# MTRduino_Rev1_0.net
KiCad netlist of a schematic drawn in EAGLE
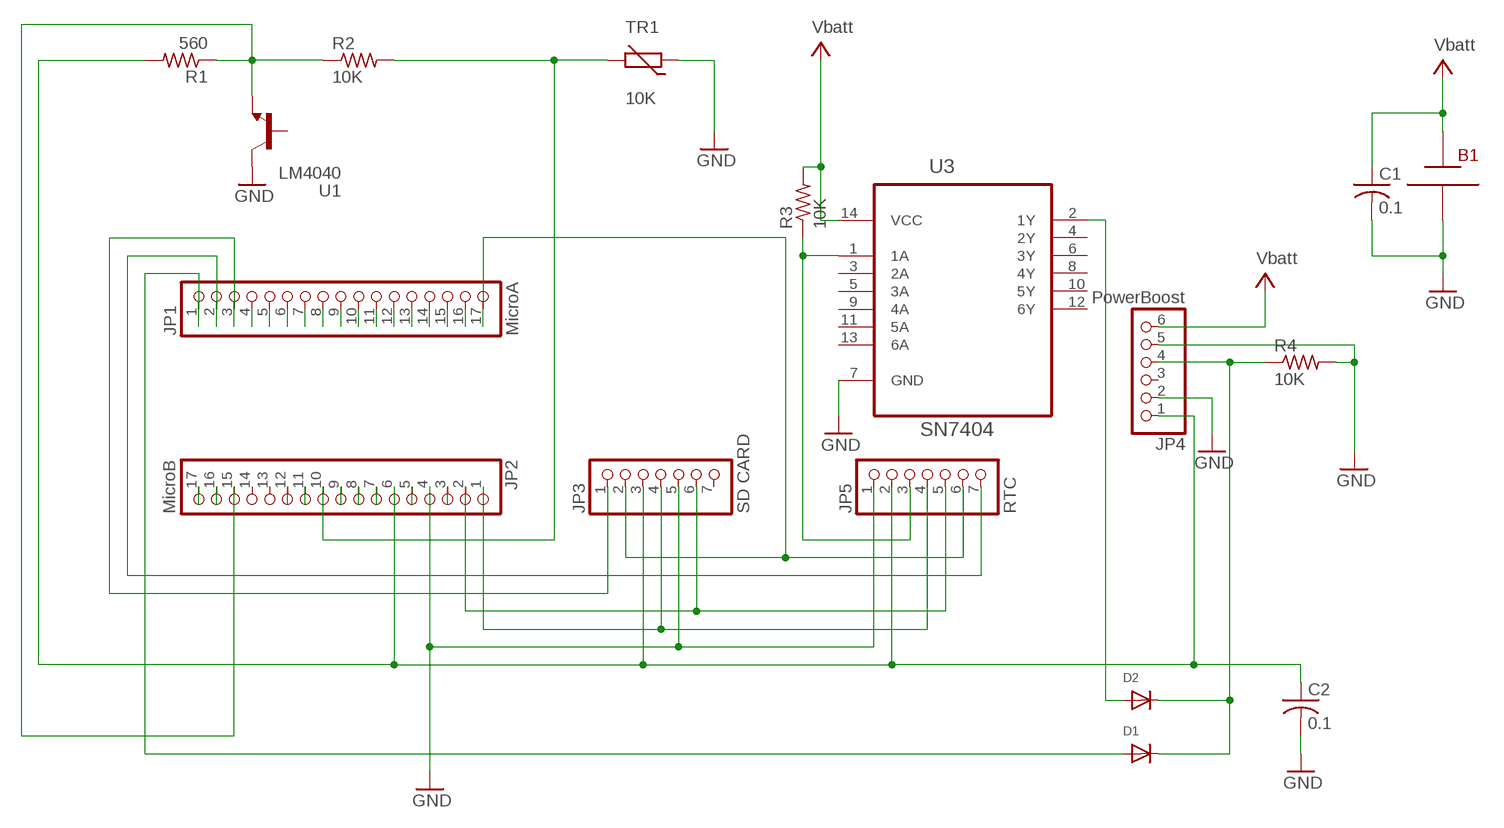
[diagram p0: schematic, sheet 1]

(export (version "E")
  (design (tool "Eeschema 10.0.6"))
  (components
    (comp (ref "B1")
      (value "AA Batt")
      (footprint "eagle-import:BATT_AA2")
      (libsource (lib "eagle-import") (part "BATT_AA2"))
    )
    (comp (ref "C1")
      (value "0.1")
      (footprint "eagle-import:C025-030X050")
      (libsource (lib "eagle-import") (part "C-US025-030X050"))
    )
    (comp (ref "C2")
      (value "0.1")
      (footprint "eagle-import:C025-030X050")
      (libsource (lib "eagle-import") (part "C-US025-030X050"))
    )
    (comp (ref "D1")
      (value "DIODEDO-1N4148")
      (footprint "eagle-import:DO-1N4148")
      (libsource (lib "eagle-import") (part "DIODEDO-1N4148"))
    )
    (comp (ref "D2")
      (value "DIODEDO-1N4148")
      (footprint "eagle-import:DO-1N4148")
      (libsource (lib "eagle-import") (part "DIODEDO-1N4148"))
    )
    (comp (ref "JP1")
      (value "MicroA")
      (footprint "eagle-import:1X17")
      (libsource (lib "eagle-import") (part "PINHD-1X17"))
    )
    (comp (ref "JP2")
      (value "MicroB")
      (footprint "eagle-import:1X17")
      (libsource (lib "eagle-import") (part "PINHD-1X17"))
    )
    (comp (ref "JP3")
      (value "SD CARD")
      (footprint "eagle-import:1X07")
      (libsource (lib "eagle-import") (part "PINHD-1X7"))
    )
    (comp (ref "JP4")
      (value "PowerBoost")
      (footprint "eagle-import:1X06")
      (libsource (lib "eagle-import") (part "PINHD-1X6"))
    )
    (comp (ref "JP5")
      (value "RTC")
      (footprint "eagle-import:1X07")
      (libsource (lib "eagle-import") (part "PINHD-1X7"))
    )
    (comp (ref "R1")
      (value "560")
      (footprint "eagle-import:0207_12")
      (libsource (lib "eagle-import") (part "R-US_0207/12"))
    )
    (comp (ref "R2")
      (value "10K")
      (footprint "eagle-import:0207_12")
      (libsource (lib "eagle-import") (part "R-US_0207/12"))
    )
    (comp (ref "R3")
      (value "10K")
      (footprint "eagle-import:0207_12")
      (libsource (lib "eagle-import") (part "R-US_0207/12"))
    )
    (comp (ref "R4")
      (value "10K")
      (footprint "eagle-import:0207_12")
      (libsource (lib "eagle-import") (part "R-US_0207/12"))
    )
    (comp (ref "TR1")
      (value "10K")
      (footprint "eagle-import:R-5")
      (libsource (lib "eagle-import") (part "THERMISTOR-5"))
    )
    (comp (ref "U1")
      (value "LM4040")
      (footprint "eagle-import:TO92-BEC")
      (libsource (lib "eagle-import") (part "-NPN-TO92-BEC"))
    )
    (comp (ref "U3")
      (value "SN7404")
      (footprint "eagle-import:DIP254P762X508-14")
      (fields (field (name "MPN") "SN74AC04N"))
      (libsource (lib "eagle-import") (part "SN74AC04N"))
    )
  )
  (nets
    (net (code "1") (name "GND") (class "Default")
      (node (ref "B1") (pin "-") (pinfunction "-_-") (pintype "bidirectional"))
      (node (ref "C1") (pin "2") (pinfunction "2_2") (pintype "passive"))
      (node (ref "C2") (pin "2") (pinfunction "2_2") (pintype "passive"))
      (node (ref "JP2") (pin "4") (pinfunction "4_4") (pintype "passive"))
      (node (ref "JP3") (pin "5") (pinfunction "5_5") (pintype "passive"))
      (node (ref "JP4") (pin "2") (pinfunction "2_2") (pintype "passive"))
      (node (ref "JP4") (pin "5") (pinfunction "5_5") (pintype "passive"))
      (node (ref "JP5") (pin "1") (pinfunction "1_1") (pintype "passive"))
      (node (ref "R4") (pin "2") (pinfunction "2_2") (pintype "passive"))
      (node (ref "TR1") (pin "1") (pinfunction "1_1") (pintype "passive"))
      (node (ref "U1") (pin "C") (pinfunction "C_C") (pintype "passive"))
      (node (ref "U3") (pin "7") (pinfunction "GND_7") (pintype "passive"))
    )
    (net (code "2") (name "Net-(C2-Pad1)") (class "Default")
      (node (ref "C2") (pin "1") (pinfunction "1_1") (pintype "passive"))
      (node (ref "JP2") (pin "6") (pinfunction "6_6") (pintype "passive"))
      (node (ref "JP3") (pin "3") (pinfunction "3_3") (pintype "passive"))
      (node (ref "JP4") (pin "1") (pinfunction "1_1") (pintype "passive"))
      (node (ref "JP5") (pin "2") (pinfunction "2_2") (pintype "passive"))
      (node (ref "R1") (pin "2") (pinfunction "2_2") (pintype "passive"))
    )
    (net (code "3") (name "Net-(D1-PadA)") (class "Default")
      (node (ref "D1") (pin "A") (pinfunction "A_A") (pintype "passive"))
      (node (ref "JP1") (pin "1") (pinfunction "1_1") (pintype "passive"))
    )
    (net (code "4") (name "Net-(D1-PadC)") (class "Default")
      (node (ref "D1") (pin "C") (pinfunction "C_C") (pintype "passive"))
      (node (ref "D2") (pin "C") (pinfunction "C_C") (pintype "passive"))
      (node (ref "JP4") (pin "4") (pinfunction "4_4") (pintype "passive"))
      (node (ref "R4") (pin "1") (pinfunction "1_1") (pintype "passive"))
    )
    (net (code "5") (name "Net-(JP1-Pad2)") (class "Default")
      (node (ref "JP1") (pin "2") (pinfunction "2_2") (pintype "passive"))
      (node (ref "JP5") (pin "7") (pinfunction "7_7") (pintype "passive"))
    )
    (net (code "6") (name "Net-(JP1-Pad3)") (class "Default")
      (node (ref "JP1") (pin "3") (pinfunction "3_3") (pintype "passive"))
      (node (ref "JP3") (pin "1") (pinfunction "1_1") (pintype "passive"))
    )
    (net (code "7") (name "Net-(JP1-Pad17)") (class "Default")
      (node (ref "JP1") (pin "17") (pinfunction "17_17") (pintype "passive"))
      (node (ref "JP3") (pin "2") (pinfunction "2_2") (pintype "passive"))
      (node (ref "JP5") (pin "6") (pinfunction "6_6") (pintype "passive"))
    )
    (net (code "8") (name "Net-(JP2-Pad1)") (class "Default")
      (node (ref "JP2") (pin "1") (pinfunction "1_1") (pintype "passive"))
      (node (ref "JP3") (pin "4") (pinfunction "4_4") (pintype "passive"))
      (node (ref "JP5") (pin "4") (pinfunction "4_4") (pintype "passive"))
    )
    (net (code "9") (name "Net-(JP2-Pad2)") (class "Default")
      (node (ref "JP2") (pin "2") (pinfunction "2_2") (pintype "passive"))
      (node (ref "JP3") (pin "6") (pinfunction "6_6") (pintype "passive"))
      (node (ref "JP5") (pin "5") (pinfunction "5_5") (pintype "passive"))
    )
    (net (code "10") (name "Net-(JP2-Pad10)") (class "Default")
      (node (ref "JP2") (pin "10") (pinfunction "10_10") (pintype "passive"))
      (node (ref "R2") (pin "2") (pinfunction "2_2") (pintype "passive"))
      (node (ref "TR1") (pin "2") (pinfunction "2_2") (pintype "passive"))
    )
    (net (code "11") (name "Net-(JP2-Pad15)") (class "Default")
      (node (ref "JP2") (pin "15") (pinfunction "15_15") (pintype "passive"))
      (node (ref "R1") (pin "1") (pinfunction "1_1") (pintype "passive"))
      (node (ref "R2") (pin "1") (pinfunction "1_1") (pintype "passive"))
      (node (ref "U1") (pin "E") (pinfunction "E_E") (pintype "passive"))
    )
    (net (code "12") (name "Net-(U3-1A)") (class "Default")
      (node (ref "JP5") (pin "3") (pinfunction "3_3") (pintype "passive"))
      (node (ref "R3") (pin "1") (pinfunction "1_1") (pintype "passive"))
      (node (ref "U3") (pin "1") (pinfunction "1A_1") (pintype "input"))
    )
    (net (code "13") (name "Net-(U3-1Y)") (class "Default")
      (node (ref "D2") (pin "A") (pinfunction "A_A") (pintype "passive"))
      (node (ref "U3") (pin "2") (pinfunction "1Y_2") (pintype "output"))
    )
    (net (code "14") (name "Vbatt") (class "Default")
      (node (ref "B1") (pin "+") (pinfunction "+_+") (pintype "bidirectional"))
      (node (ref "C1") (pin "1") (pinfunction "1_1") (pintype "passive"))
      (node (ref "JP4") (pin "6") (pinfunction "6_6") (pintype "passive"))
      (node (ref "R3") (pin "2") (pinfunction "2_2") (pintype "passive"))
      (node (ref "U3") (pin "14") (pinfunction "VCC_14") (pintype "power_in"))
    )
    (net (code "15") (name "unconnected-(JP1-Pad4)") (class "Default")
      (node (ref "JP1") (pin "4") (pinfunction "4_4") (pintype "passive"))
    )
    (net (code "16") (name "unconnected-(JP1-Pad5)") (class "Default")
      (node (ref "JP1") (pin "5") (pinfunction "5_5") (pintype "passive"))
    )
    (net (code "17") (name "unconnected-(JP1-Pad6)") (class "Default")
      (node (ref "JP1") (pin "6") (pinfunction "6_6") (pintype "passive"))
    )
    (net (code "18") (name "unconnected-(JP1-Pad7)") (class "Default")
      (node (ref "JP1") (pin "7") (pinfunction "7_7") (pintype "passive"))
    )
    (net (code "19") (name "unconnected-(JP1-Pad8)") (class "Default")
      (node (ref "JP1") (pin "8") (pinfunction "8_8") (pintype "passive"))
    )
    (net (code "20") (name "unconnected-(JP1-Pad9)") (class "Default")
      (node (ref "JP1") (pin "9") (pinfunction "9_9") (pintype "passive"))
    )
    (net (code "21") (name "unconnected-(JP1-Pad10)") (class "Default")
      (node (ref "JP1") (pin "10") (pinfunction "10_10") (pintype "passive"))
    )
    (net (code "22") (name "unconnected-(JP1-Pad11)") (class "Default")
      (node (ref "JP1") (pin "11") (pinfunction "11_11") (pintype "passive"))
    )
    (net (code "23") (name "unconnected-(JP1-Pad12)") (class "Default")
      (node (ref "JP1") (pin "12") (pinfunction "12_12") (pintype "passive"))
    )
    (net (code "24") (name "unconnected-(JP1-Pad13)") (class "Default")
      (node (ref "JP1") (pin "13") (pinfunction "13_13") (pintype "passive"))
    )
    (net (code "25") (name "unconnected-(JP1-Pad14)") (class "Default")
      (node (ref "JP1") (pin "14") (pinfunction "14_14") (pintype "passive"))
    )
    (net (code "26") (name "unconnected-(JP1-Pad15)") (class "Default")
      (node (ref "JP1") (pin "15") (pinfunction "15_15") (pintype "passive"))
    )
    (net (code "27") (name "unconnected-(JP1-Pad16)") (class "Default")
      (node (ref "JP1") (pin "16") (pinfunction "16_16") (pintype "passive"))
    )
    (net (code "28") (name "unconnected-(JP2-Pad3)") (class "Default")
      (node (ref "JP2") (pin "3") (pinfunction "3_3") (pintype "passive"))
    )
    (net (code "29") (name "unconnected-(JP2-Pad5)") (class "Default")
      (node (ref "JP2") (pin "5") (pinfunction "5_5") (pintype "passive"))
    )
    (net (code "30") (name "unconnected-(JP2-Pad7)") (class "Default")
      (node (ref "JP2") (pin "7") (pinfunction "7_7") (pintype "passive"))
    )
    (net (code "31") (name "unconnected-(JP2-Pad8)") (class "Default")
      (node (ref "JP2") (pin "8") (pinfunction "8_8") (pintype "passive"))
    )
    (net (code "32") (name "unconnected-(JP2-Pad9)") (class "Default")
      (node (ref "JP2") (pin "9") (pinfunction "9_9") (pintype "passive"))
    )
    (net (code "33") (name "unconnected-(JP2-Pad11)") (class "Default")
      (node (ref "JP2") (pin "11") (pinfunction "11_11") (pintype "passive"))
    )
    (net (code "34") (name "unconnected-(JP2-Pad12)") (class "Default")
      (node (ref "JP2") (pin "12") (pinfunction "12_12") (pintype "passive"))
    )
    (net (code "35") (name "unconnected-(JP2-Pad13)") (class "Default")
      (node (ref "JP2") (pin "13") (pinfunction "13_13") (pintype "passive"))
    )
    (net (code "36") (name "unconnected-(JP2-Pad14)") (class "Default")
      (node (ref "JP2") (pin "14") (pinfunction "14_14") (pintype "passive"))
    )
    (net (code "37") (name "unconnected-(JP2-Pad16)") (class "Default")
      (node (ref "JP2") (pin "16") (pinfunction "16_16") (pintype "passive"))
    )
    (net (code "38") (name "unconnected-(JP2-Pad17)") (class "Default")
      (node (ref "JP2") (pin "17") (pinfunction "17_17") (pintype "passive"))
    )
    (net (code "39") (name "unconnected-(JP3-Pad7)") (class "Default")
      (node (ref "JP3") (pin "7") (pinfunction "7_7") (pintype "passive"))
    )
    (net (code "40") (name "unconnected-(JP4-Pad3)") (class "Default")
      (node (ref "JP4") (pin "3") (pinfunction "3_3") (pintype "passive"))
    )
    (net (code "41") (name "unconnected-(U1-PadB)") (class "Default")
      (node (ref "U1") (pin "B") (pinfunction "B_B") (pintype "passive"))
    )
    (net (code "42") (name "unconnected-(U3-2A-Pad3)") (class "Default")
      (node (ref "U3") (pin "3") (pinfunction "2A_3") (pintype "input"))
    )
    (net (code "43") (name "unconnected-(U3-2Y-Pad4)") (class "Default")
      (node (ref "U3") (pin "4") (pinfunction "2Y_4") (pintype "output"))
    )
    (net (code "44") (name "unconnected-(U3-3A-Pad5)") (class "Default")
      (node (ref "U3") (pin "5") (pinfunction "3A_5") (pintype "input"))
    )
    (net (code "45") (name "unconnected-(U3-3Y-Pad6)") (class "Default")
      (node (ref "U3") (pin "6") (pinfunction "3Y_6") (pintype "output"))
    )
    (net (code "46") (name "unconnected-(U3-4A-Pad9)") (class "Default")
      (node (ref "U3") (pin "9") (pinfunction "4A_9") (pintype "input"))
    )
    (net (code "47") (name "unconnected-(U3-4Y-Pad8)") (class "Default")
      (node (ref "U3") (pin "8") (pinfunction "4Y_8") (pintype "output"))
    )
    (net (code "48") (name "unconnected-(U3-5A-Pad11)") (class "Default")
      (node (ref "U3") (pin "11") (pinfunction "5A_11") (pintype "input"))
    )
    (net (code "49") (name "unconnected-(U3-5Y-Pad10)") (class "Default")
      (node (ref "U3") (pin "10") (pinfunction "5Y_10") (pintype "output"))
    )
    (net (code "50") (name "unconnected-(U3-6A-Pad13)") (class "Default")
      (node (ref "U3") (pin "13") (pinfunction "6A_13") (pintype "input"))
    )
    (net (code "51") (name "unconnected-(U3-6Y-Pad12)") (class "Default")
      (node (ref "U3") (pin "12") (pinfunction "6Y_12") (pintype "output"))
    )
  )
)
